# Sram2FramAdapter.net
KiCad netlist of a schematic drawn in EAGLE
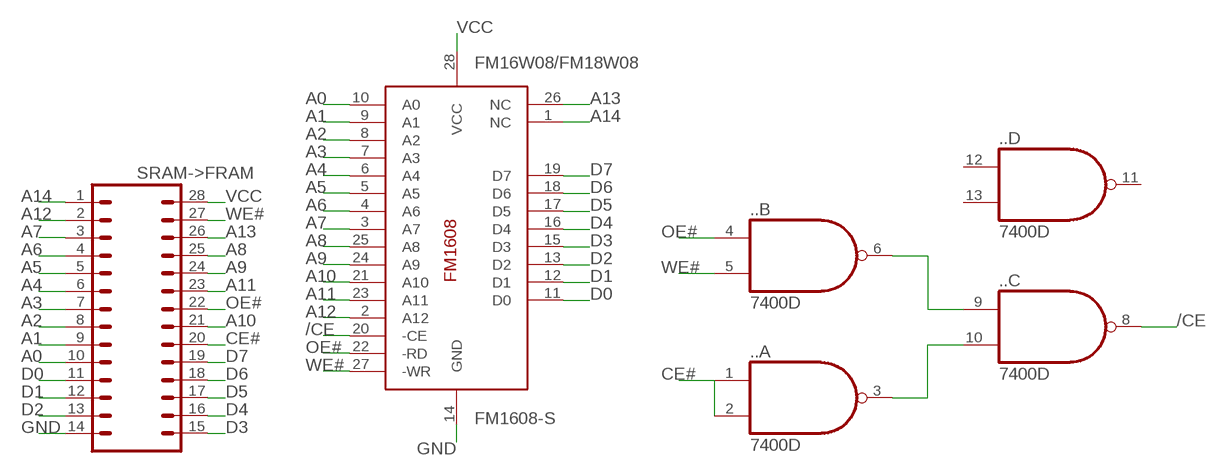
[diagram p0: schematic, sheet 1]

(export (version "E")
  (design (tool "Eeschema 10.0.6"))
  (components
    (comp (ref "..")
      (value "7400D")
      (footprint "eagle-import:SO14")
      (libsource (lib "eagle-import") (part "7400D"))
    )
    (comp (ref "FM16W08/FM18W08")
      (value "FM1608-S")
      (footprint "eagle-import:SO-28W")
      (libsource (lib "eagle-import") (part "FM1608-S"))
    )
    (comp (ref "SRAM->FRAM")
      (value "DIP28PTH")
      (footprint "eagle-import:DIP28")
      (libsource (lib "eagle-import") (part "DIP28PTH"))
    )
  )
  (nets
    (net (code "1") (name "/A0") (class "Default")
      (node (ref "FM16W08/FM18W08") (pin "10") (pinfunction "A0_10") (pintype "input"))
      (node (ref "SRAM->FRAM") (pin "10") (pinfunction "10_10") (pintype "passive"))
    )
    (net (code "2") (name "/A1") (class "Default")
      (node (ref "FM16W08/FM18W08") (pin "9") (pinfunction "A1_9") (pintype "input"))
      (node (ref "SRAM->FRAM") (pin "9") (pinfunction "9_9") (pintype "passive"))
    )
    (net (code "3") (name "/A2") (class "Default")
      (node (ref "FM16W08/FM18W08") (pin "8") (pinfunction "A2_8") (pintype "input"))
      (node (ref "SRAM->FRAM") (pin "8") (pinfunction "8_8") (pintype "passive"))
    )
    (net (code "4") (name "/A3") (class "Default")
      (node (ref "FM16W08/FM18W08") (pin "7") (pinfunction "A3_7") (pintype "input"))
      (node (ref "SRAM->FRAM") (pin "7") (pinfunction "7_7") (pintype "passive"))
    )
    (net (code "5") (name "/A4") (class "Default")
      (node (ref "FM16W08/FM18W08") (pin "6") (pinfunction "A4_6") (pintype "input"))
      (node (ref "SRAM->FRAM") (pin "6") (pinfunction "6_6") (pintype "passive"))
    )
    (net (code "6") (name "/A5") (class "Default")
      (node (ref "FM16W08/FM18W08") (pin "5") (pinfunction "A5_5") (pintype "input"))
      (node (ref "SRAM->FRAM") (pin "5") (pinfunction "5_5") (pintype "passive"))
    )
    (net (code "7") (name "/A6") (class "Default")
      (node (ref "FM16W08/FM18W08") (pin "4") (pinfunction "A6_4") (pintype "input"))
      (node (ref "SRAM->FRAM") (pin "4") (pinfunction "4_4") (pintype "passive"))
    )
    (net (code "8") (name "/A7") (class "Default")
      (node (ref "FM16W08/FM18W08") (pin "3") (pinfunction "A7_3") (pintype "input"))
      (node (ref "SRAM->FRAM") (pin "3") (pinfunction "3_3") (pintype "passive"))
    )
    (net (code "9") (name "/A8") (class "Default")
      (node (ref "FM16W08/FM18W08") (pin "25") (pinfunction "A8_25") (pintype "input"))
      (node (ref "SRAM->FRAM") (pin "25") (pinfunction "25_25") (pintype "passive"))
    )
    (net (code "10") (name "/A9") (class "Default")
      (node (ref "FM16W08/FM18W08") (pin "24") (pinfunction "A9_24") (pintype "input"))
      (node (ref "SRAM->FRAM") (pin "24") (pinfunction "24_24") (pintype "passive"))
    )
    (net (code "11") (name "/A10") (class "Default")
      (node (ref "FM16W08/FM18W08") (pin "21") (pinfunction "A10_21") (pintype "input"))
      (node (ref "SRAM->FRAM") (pin "21") (pinfunction "21_21") (pintype "passive"))
    )
    (net (code "12") (name "/A11") (class "Default")
      (node (ref "FM16W08/FM18W08") (pin "23") (pinfunction "A11_23") (pintype "input"))
      (node (ref "SRAM->FRAM") (pin "23") (pinfunction "23_23") (pintype "passive"))
    )
    (net (code "13") (name "/A12") (class "Default")
      (node (ref "FM16W08/FM18W08") (pin "2") (pinfunction "A12_2") (pintype "input"))
      (node (ref "SRAM->FRAM") (pin "2") (pinfunction "2_2") (pintype "passive"))
    )
    (net (code "14") (name "/A13") (class "Default")
      (node (ref "FM16W08/FM18W08") (pin "26") (pinfunction "NC_26") (pintype "passive"))
      (node (ref "SRAM->FRAM") (pin "26") (pinfunction "26_26") (pintype "passive"))
    )
    (net (code "15") (name "/A14") (class "Default")
      (node (ref "FM16W08/FM18W08") (pin "1") (pinfunction "NC_1") (pintype "passive"))
      (node (ref "SRAM->FRAM") (pin "1") (pinfunction "1_1") (pintype "passive"))
    )
    (net (code "16") (name "/CE#") (class "Default")
      (node (ref "..") (pin "1") (pinfunction "I0_1") (pintype "input"))
      (node (ref "..") (pin "2") (pinfunction "I1_2") (pintype "input"))
      (node (ref "SRAM->FRAM") (pin "20") (pinfunction "20_20") (pintype "passive"))
    )
    (net (code "17") (name "/D0") (class "Default")
      (node (ref "FM16W08/FM18W08") (pin "11") (pinfunction "D0_11") (pintype "bidirectional"))
      (node (ref "SRAM->FRAM") (pin "11") (pinfunction "11_11") (pintype "passive"))
    )
    (net (code "18") (name "/D1") (class "Default")
      (node (ref "FM16W08/FM18W08") (pin "12") (pinfunction "D1_12") (pintype "bidirectional"))
      (node (ref "SRAM->FRAM") (pin "12") (pinfunction "12_12") (pintype "passive"))
    )
    (net (code "19") (name "/D2") (class "Default")
      (node (ref "FM16W08/FM18W08") (pin "13") (pinfunction "D2_13") (pintype "bidirectional"))
      (node (ref "SRAM->FRAM") (pin "13") (pinfunction "13_13") (pintype "passive"))
    )
    (net (code "20") (name "/D3") (class "Default")
      (node (ref "FM16W08/FM18W08") (pin "15") (pinfunction "D3_15") (pintype "bidirectional"))
      (node (ref "SRAM->FRAM") (pin "15") (pinfunction "15_15") (pintype "passive"))
    )
    (net (code "21") (name "/D4") (class "Default")
      (node (ref "FM16W08/FM18W08") (pin "16") (pinfunction "D4_16") (pintype "bidirectional"))
      (node (ref "SRAM->FRAM") (pin "16") (pinfunction "16_16") (pintype "passive"))
    )
    (net (code "22") (name "/D5") (class "Default")
      (node (ref "FM16W08/FM18W08") (pin "17") (pinfunction "D5_17") (pintype "bidirectional"))
      (node (ref "SRAM->FRAM") (pin "17") (pinfunction "17_17") (pintype "passive"))
    )
    (net (code "23") (name "/D6") (class "Default")
      (node (ref "FM16W08/FM18W08") (pin "18") (pinfunction "D6_18") (pintype "bidirectional"))
      (node (ref "SRAM->FRAM") (pin "18") (pinfunction "18_18") (pintype "passive"))
    )
    (net (code "24") (name "/D7") (class "Default")
      (node (ref "FM16W08/FM18W08") (pin "19") (pinfunction "D7_19") (pintype "bidirectional"))
      (node (ref "SRAM->FRAM") (pin "19") (pinfunction "19_19") (pintype "passive"))
    )
    (net (code "25") (name "/GND") (class "Default")
      (node (ref "FM16W08/FM18W08") (pin "14") (pinfunction "GND_14") (pintype "power_in"))
      (node (ref "SRAM->FRAM") (pin "14") (pinfunction "14_14") (pintype "passive"))
    )
    (net (code "26") (name "/OE#") (class "Default")
      (node (ref "..") (pin "4") (pinfunction "I0_4") (pintype "input"))
      (node (ref "FM16W08/FM18W08") (pin "22") (pinfunction "-RD_22") (pintype "input"))
      (node (ref "SRAM->FRAM") (pin "22") (pinfunction "22_22") (pintype "passive"))
    )
    (net (code "27") (name "/VCC") (class "Default")
      (node (ref "FM16W08/FM18W08") (pin "28") (pinfunction "VCC_28") (pintype "power_in"))
      (node (ref "SRAM->FRAM") (pin "28") (pinfunction "28_28") (pintype "passive"))
    )
    (net (code "28") (name "/WE#") (class "Default")
      (node (ref "..") (pin "5") (pinfunction "I1_5") (pintype "input"))
      (node (ref "FM16W08/FM18W08") (pin "27") (pinfunction "-WR_27") (pintype "input"))
      (node (ref "SRAM->FRAM") (pin "27") (pinfunction "27_27") (pintype "passive"))
    )
    (net (code "29") (name "/{slash}CE") (class "Default")
      (node (ref "..") (pin "8") (pinfunction "O_8") (pintype "output"))
      (node (ref "FM16W08/FM18W08") (pin "20") (pinfunction "-CE_20") (pintype "input"))
    )
    (net (code "30") (name "Net-(..A-O)") (class "Default")
      (node (ref "..") (pin "10") (pinfunction "I1_10") (pintype "input"))
      (node (ref "..") (pin "3") (pinfunction "O_3") (pintype "output"))
    )
    (net (code "31") (name "Net-(..B-O)") (class "Default")
      (node (ref "..") (pin "6") (pinfunction "O_6") (pintype "output"))
      (node (ref "..") (pin "9") (pinfunction "I0_9") (pintype "input"))
    )
    (net (code "32") (name "unconnected-(..D-I0-Pad12)") (class "Default")
      (node (ref "..") (pin "12") (pinfunction "I0_12") (pintype "input"))
    )
    (net (code "33") (name "unconnected-(..D-I1-Pad13)") (class "Default")
      (node (ref "..") (pin "13") (pinfunction "I1_13") (pintype "input"))
    )
    (net (code "34") (name "unconnected-(..D-O-Pad11)") (class "Default")
      (node (ref "..") (pin "11") (pinfunction "O_11") (pintype "output"))
    )
  )
)
